# Reguladores.net
KiCad netlist of a schematic drawn in Altium Designer
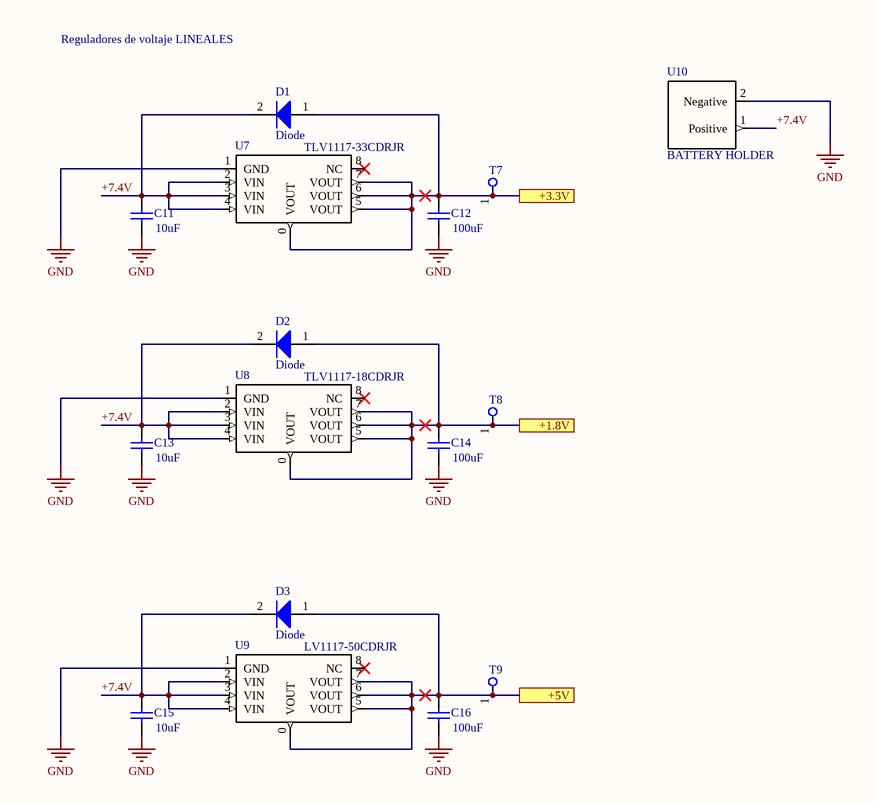
[diagram p0: Reguladores.SchDoc]

(export (version "E")
  (design (tool "Eeschema 10.0.6"))
  (components
    (comp (ref "C11")
      (value "10uF")
      (footprint "0603 Cap")
      (fields (field (name "Comment") "Cap"))
      (libsource (lib "B105rlc") (part "Cap"))
    )
    (comp (ref "C12")
      (value "100uF")
      (footprint "3216 Tantalum")
      (fields (field (name "Comment") "Cap"))
      (libsource (lib "B105rlc") (part "Cap"))
    )
    (comp (ref "C13")
      (value "10uF")
      (footprint "0603 Cap")
      (fields (field (name "Comment") "Cap"))
      (libsource (lib "B105rlc") (part "Cap"))
    )
    (comp (ref "C14")
      (value "100uF")
      (footprint "3216 Tantalum")
      (fields (field (name "Comment") "Cap"))
      (libsource (lib "B105rlc") (part "Cap"))
    )
    (comp (ref "C15")
      (value "10uF")
      (footprint "0603 Cap")
      (fields (field (name "Comment") "Cap"))
      (libsource (lib "B105rlc") (part "Cap"))
    )
    (comp (ref "C16")
      (value "100uF")
      (footprint "3216 Tantalum")
      (fields (field (name "Comment") "Cap"))
      (libsource (lib "B105rlc") (part "Cap"))
    )
    (comp (ref "D1") (value "Diode") (footprint "SOD-123") (libsource (lib "B105rlc") (part "Diode")))
    (comp (ref "D2") (value "Diode") (footprint "SOD-123") (libsource (lib "B105rlc") (part "Diode")))
    (comp (ref "D3") (value "Diode") (footprint "SOD-123") (libsource (lib "B105rlc") (part "Diode")))
    (comp (ref "T7")
      (value "testpoint")
      (footprint "testpoint")
      (libsource (lib "Libreria Nuria") (part "testpoint"))
    )
    (comp (ref "T8")
      (value "testpoint")
      (footprint "testpoint")
      (libsource (lib "Libreria Nuria") (part "testpoint"))
    )
    (comp (ref "T9")
      (value "testpoint")
      (footprint "testpoint")
      (libsource (lib "Libreria Nuria") (part "testpoint"))
    )
    (comp (ref "U7")
      (value "TLV1117-33CDRJR")
      (footprint "TLV1117")
      (libsource (lib "Libreria Nuria") (part "TLV1117"))
    )
    (comp (ref "U8")
      (value "TLV1117-18CDRJR")
      (footprint "TLV1117")
      (libsource (lib "Libreria Nuria") (part "TLV1117"))
    )
    (comp (ref "U9")
      (value "LV1117-50CDRJR")
      (footprint "TLV1117")
      (libsource (lib "Libreria Nuria") (part "TLV1117"))
    )
    (comp (ref "U10")
      (value "BATTERY HOLDER")
      (footprint "battery holder 224")
      (libsource (lib "Libreria Nuria") (part "BATTERY HOLDER"))
    )
  )
  (nets
    (net (code "1") (name "/+1.8V") (class "Default")
      (node (ref "C14") (pin "2") (pinfunction "2_2") (pintype "passive"))
      (node (ref "D2") (pin "1") (pinfunction "A_1") (pintype "passive"))
      (node (ref "T8") (pin "1") (pinfunction "TP_1") (pintype "passive"))
      (node (ref "U8") (pin "0") (pinfunction "VOUT_0") (pintype "output"))
      (node (ref "U8") (pin "5") (pinfunction "VOUT_5") (pintype "output"))
      (node (ref "U8") (pin "6") (pinfunction "VOUT_6") (pintype "output"))
      (node (ref "U8") (pin "7") (pinfunction "VOUT_7") (pintype "output"))
    )
    (net (code "2") (name "/+3.3V") (class "Default")
      (node (ref "C12") (pin "2") (pinfunction "2_2") (pintype "passive"))
      (node (ref "D1") (pin "1") (pinfunction "A_1") (pintype "passive"))
      (node (ref "T7") (pin "1") (pinfunction "TP_1") (pintype "passive"))
      (node (ref "U7") (pin "0") (pinfunction "VOUT_0") (pintype "output"))
      (node (ref "U7") (pin "5") (pinfunction "VOUT_5") (pintype "output"))
      (node (ref "U7") (pin "6") (pinfunction "VOUT_6") (pintype "output"))
      (node (ref "U7") (pin "7") (pinfunction "VOUT_7") (pintype "output"))
    )
    (net (code "3") (name "/+5V") (class "Default")
      (node (ref "C16") (pin "2") (pinfunction "2_2") (pintype "passive"))
      (node (ref "D3") (pin "1") (pinfunction "A_1") (pintype "passive"))
      (node (ref "T9") (pin "1") (pinfunction "TP_1") (pintype "passive"))
      (node (ref "U9") (pin "0") (pinfunction "VOUT_0") (pintype "output"))
      (node (ref "U9") (pin "5") (pinfunction "VOUT_5") (pintype "output"))
      (node (ref "U9") (pin "6") (pinfunction "VOUT_6") (pintype "output"))
      (node (ref "U9") (pin "7") (pinfunction "VOUT_7") (pintype "output"))
    )
    (net (code "4") (name "/+7.4V") (class "Default")
      (node (ref "C11") (pin "2") (pinfunction "2_2") (pintype "passive"))
      (node (ref "C13") (pin "2") (pinfunction "2_2") (pintype "passive"))
      (node (ref "C15") (pin "2") (pinfunction "2_2") (pintype "passive"))
      (node (ref "D1") (pin "2") (pinfunction "C_2") (pintype "passive"))
      (node (ref "D2") (pin "2") (pinfunction "C_2") (pintype "passive"))
      (node (ref "D3") (pin "2") (pinfunction "C_2") (pintype "passive"))
      (node (ref "U10") (pin "1") (pinfunction "Positive_1") (pintype "output"))
      (node (ref "U7") (pin "2") (pinfunction "VIN_2") (pintype "input"))
      (node (ref "U7") (pin "3") (pinfunction "VIN_3") (pintype "input"))
      (node (ref "U7") (pin "4") (pinfunction "VIN_4") (pintype "input"))
      (node (ref "U8") (pin "2") (pinfunction "VIN_2") (pintype "input"))
      (node (ref "U8") (pin "3") (pinfunction "VIN_3") (pintype "input"))
      (node (ref "U8") (pin "4") (pinfunction "VIN_4") (pintype "input"))
      (node (ref "U9") (pin "2") (pinfunction "VIN_2") (pintype "input"))
      (node (ref "U9") (pin "3") (pinfunction "VIN_3") (pintype "input"))
      (node (ref "U9") (pin "4") (pinfunction "VIN_4") (pintype "input"))
    )
    (net (code "5") (name "GND") (class "Default")
      (node (ref "C11") (pin "1") (pinfunction "1_1") (pintype "passive"))
      (node (ref "C12") (pin "1") (pinfunction "1_1") (pintype "passive"))
      (node (ref "C13") (pin "1") (pinfunction "1_1") (pintype "passive"))
      (node (ref "C14") (pin "1") (pinfunction "1_1") (pintype "passive"))
      (node (ref "C15") (pin "1") (pinfunction "1_1") (pintype "passive"))
      (node (ref "C16") (pin "1") (pinfunction "1_1") (pintype "passive"))
      (node (ref "U10") (pin "2") (pinfunction "Negative_2") (pintype "power_in"))
      (node (ref "U7") (pin "1") (pinfunction "GND_1") (pintype "power_in"))
      (node (ref "U8") (pin "1") (pinfunction "GND_1") (pintype "power_in"))
      (node (ref "U9") (pin "1") (pinfunction "GND_1") (pintype "power_in"))
    )
    (net (code "6") (name "unconnected-(U7-NC-Pad8)") (class "Default")
      (node (ref "U7") (pin "8") (pinfunction "NC_8") (pintype "passive+no_connect"))
    )
    (net (code "7") (name "unconnected-(U8-NC-Pad8)") (class "Default")
      (node (ref "U8") (pin "8") (pinfunction "NC_8") (pintype "passive+no_connect"))
    )
    (net (code "8") (name "unconnected-(U9-NC-Pad8)") (class "Default")
      (node (ref "U9") (pin "8") (pinfunction "NC_8") (pintype "passive+no_connect"))
    )
  )
)
